# 09F-02.net
KiCad netlist of a schematic drawn in EAGLE
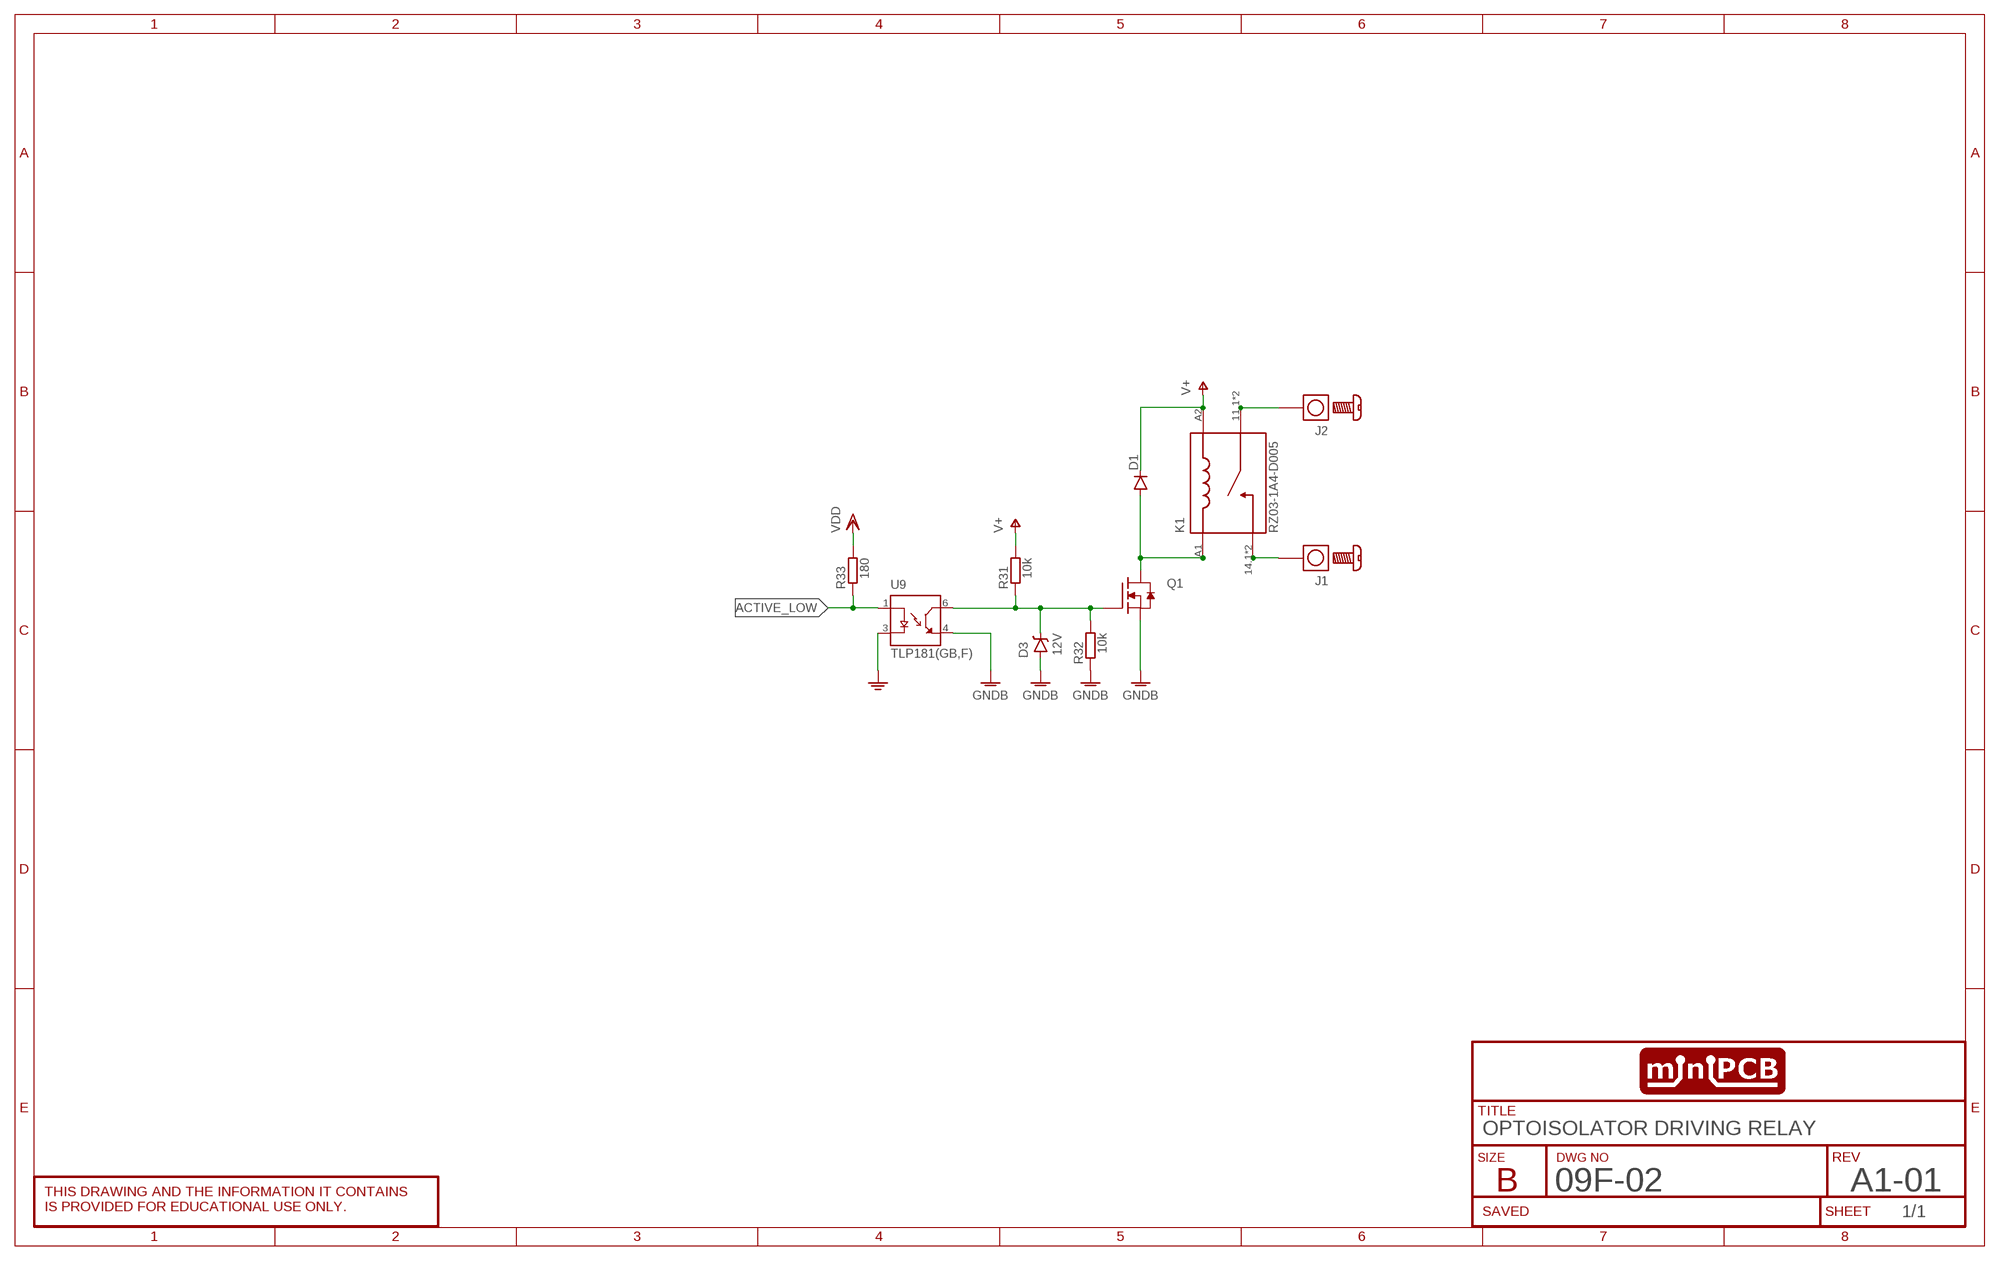
[diagram p0: schematic, sheet 1]

(export (version "E")
  (design (tool "Eeschema 10.0.6"))
  (components
    (comp (ref "D1")
      (value "DIODE-SOD323-W")
      (footprint "eagle-import:SOD323-W")
      (libsource (lib "eagle-import") (part "DIODE-SOD323-W"))
    )
    (comp (ref "D3")
      (value "12V")
      (footprint "eagle-import:SOT23")
      (libsource (lib "eagle-import") (part "ZENERSOT23"))
    )
    (comp (ref "J1")
      (value "SCREW-TERMINAL")
      (footprint "eagle-import:SCREW-TERMINAL-M3")
      (libsource (lib "eagle-import") (part "SCREW-TERMINAL"))
    )
    (comp (ref "J2")
      (value "SCREW-TERMINAL")
      (footprint "eagle-import:SCREW-TERMINAL-M3")
      (libsource (lib "eagle-import") (part "SCREW-TERMINAL"))
    )
    (comp (ref "K1")
      (value "RZ03-1A4-D005")
      (footprint "eagle-import:RELAY_RZ03-1A4-D005")
      (fields (field (name "MF") "TE Connectivity"))
      (libsource (lib "eagle-import") (part "RZ03-1A4-D005"))
    )
    (comp (ref "Q1")
      (value "MOSFET-NSOT23")
      (footprint "eagle-import:SOT23")
      (libsource (lib "eagle-import") (part "MOSFET-NSOT23"))
    )
    (comp (ref "R31")
      (value "10k")
      (footprint "eagle-import:R0805")
      (libsource (lib "eagle-import") (part "RESISTORSMD"))
    )
    (comp (ref "R32")
      (value "10k")
      (footprint "eagle-import:R0805")
      (libsource (lib "eagle-import") (part "RESISTORSMD"))
    )
    (comp (ref "R33")
      (value "180")
      (footprint "eagle-import:R0805")
      (libsource (lib "eagle-import") (part "RESISTORSMD"))
    )
    (comp (ref "U9")
      (value "TLP181(GB,F)")
      (footprint "eagle-import:SOIC254P700X280-4N")
      (fields (field (name "MF") "Toshiba"))
      (libsource (lib "eagle-import") (part "TLP181(GB,F)"))
    )
  )
  (nets
    (net (code "1") (name "ACTIVE_LOW") (class "Default")
      (node (ref "R33") (pin "1") (pinfunction "1_1") (pintype "passive"))
      (node (ref "U9") (pin "1") (pinfunction "A_1") (pintype "passive"))
    )
    (net (code "2") (name "GND") (class "Default")
      (node (ref "U9") (pin "3") (pinfunction "C_3") (pintype "passive"))
    )
    (net (code "3") (name "GNDB") (class "Default")
      (node (ref "D3") (pin "1") (pinfunction "A_1") (pintype "passive"))
      (node (ref "Q1") (pin "2") (pinfunction "S_2") (pintype "passive"))
      (node (ref "R32") (pin "1") (pinfunction "1_1") (pintype "passive"))
      (node (ref "U9") (pin "4") (pinfunction "ET_4") (pintype "passive"))
    )
    (net (code "4") (name "Net-(D3-C)") (class "Default")
      (node (ref "D3") (pin "3") (pinfunction "C_3") (pintype "passive"))
      (node (ref "Q1") (pin "1") (pinfunction "G_1") (pintype "passive"))
      (node (ref "R31") (pin "1") (pinfunction "1_1") (pintype "passive"))
      (node (ref "R32") (pin "2") (pinfunction "2_2") (pintype "passive"))
      (node (ref "U9") (pin "6") (pinfunction "CT_6") (pintype "passive"))
    )
    (net (code "5") (name "Net-(J1-1-Pad2)") (class "Default")
      (node (ref "J1") (pin "1") (pinfunction "1_1") (pintype "bidirectional"))
      (node (ref "J1") (pin "2") (pinfunction "1_2") (pintype "bidirectional"))
      (node (ref "J1") (pin "3") (pinfunction "1_3") (pintype "bidirectional"))
      (node (ref "J1") (pin "4") (pinfunction "1_4") (pintype "bidirectional"))
      (node (ref "K1") (pin "14.1") (pinfunction "14_14.1") (pintype "passive"))
      (node (ref "K1") (pin "14.2") (pinfunction "14_14.2") (pintype "passive"))
    )
    (net (code "6") (name "Net-(J2-1-Pad2)") (class "Default")
      (node (ref "J2") (pin "1") (pinfunction "1_1") (pintype "bidirectional"))
      (node (ref "J2") (pin "2") (pinfunction "1_2") (pintype "bidirectional"))
      (node (ref "J2") (pin "3") (pinfunction "1_3") (pintype "bidirectional"))
      (node (ref "J2") (pin "4") (pinfunction "1_4") (pintype "bidirectional"))
      (node (ref "K1") (pin "11.1") (pinfunction "11_11.1") (pintype "passive"))
      (node (ref "K1") (pin "11.2") (pinfunction "11_11.2") (pintype "passive"))
    )
    (net (code "7") (name "Net-(Q1-D)") (class "Default")
      (node (ref "D1") (pin "A") (pinfunction "A_A") (pintype "passive"))
      (node (ref "K1") (pin "A1") (pinfunction "A1_A1") (pintype "passive"))
      (node (ref "Q1") (pin "3") (pinfunction "D_3") (pintype "passive"))
    )
    (net (code "8") (name "V+") (class "Default")
      (node (ref "D1") (pin "C") (pinfunction "C_C") (pintype "passive"))
      (node (ref "K1") (pin "A2") (pinfunction "A2_A2") (pintype "passive"))
      (node (ref "R31") (pin "2") (pinfunction "2_2") (pintype "passive"))
    )
    (net (code "9") (name "VDD") (class "Default")
      (node (ref "R33") (pin "2") (pinfunction "2_2") (pintype "passive"))
    )
  )
)
